# Top.net
KiCad netlist of a schematic drawn in Altium Designer
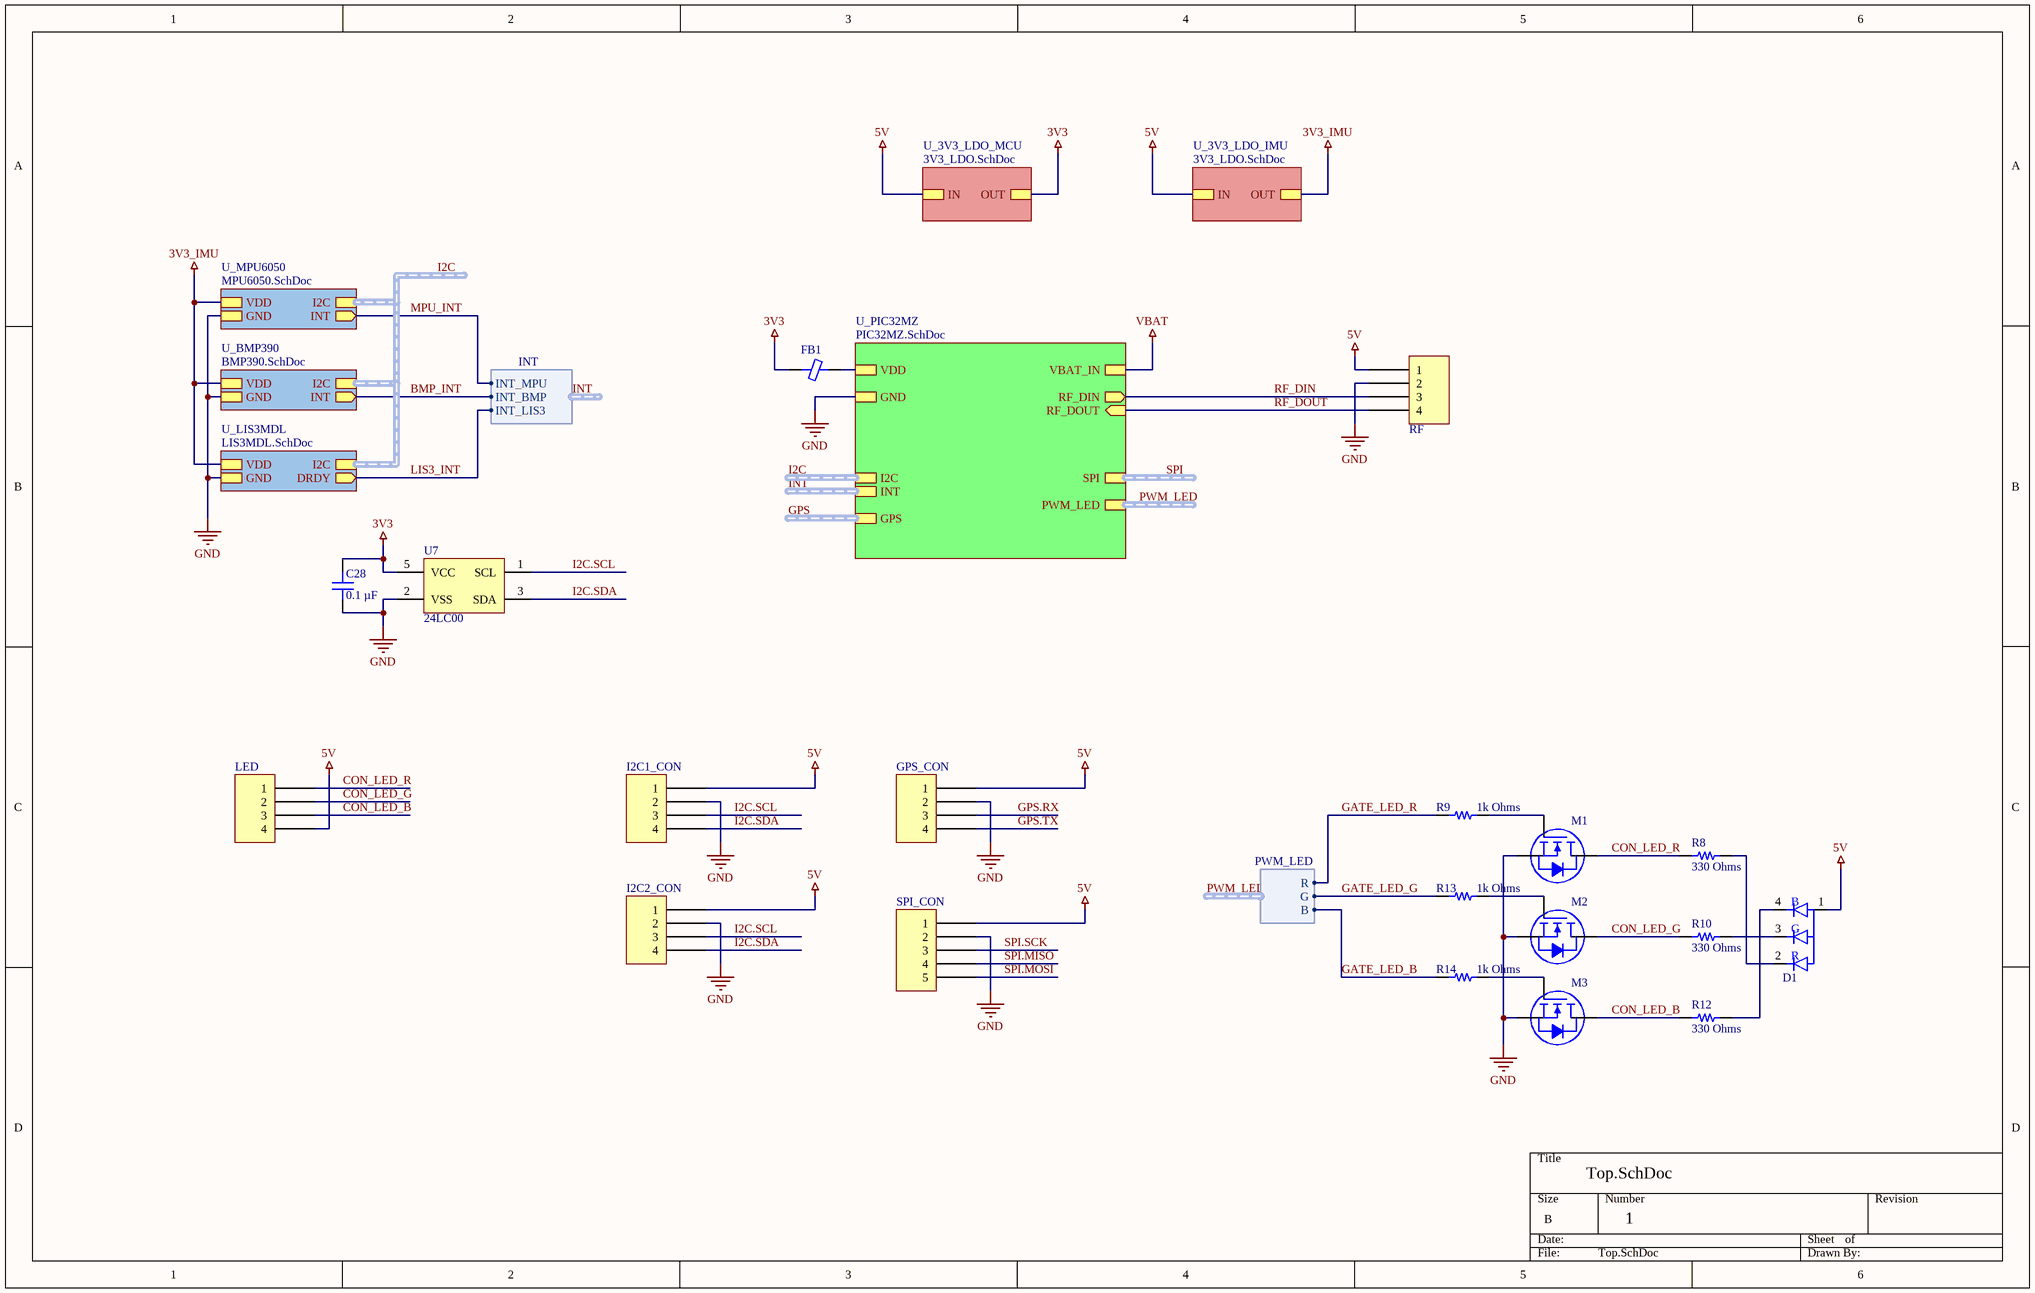
[diagram p0: Top.SchDoc]

(export (version "E")
  (design (tool "Eeschema 10.0.6"))
  (components
    (comp (ref "C28")
      (value "0.1 µF")
      (footprint "CAP 0402_1005")
      (description "CAP CER 0.1UF 16V X7R 0402")
      (fields (field (name "PART NUMBER") "C0402C104K4RACAUTO") (field (name "MANUFACTURER") "KEMET"))
      (libsource (lib "Celestial Altium Library - altium_library") (part "Capacitor"))
    )
    (comp (ref "D1")
      (value "RGB LED 3228")
      (footprint "CreeLED 3228")
      (description "DIODE LED RGB DIFFUSED 4LCC SMD CLV1L-FKB-CJ1N1E1BB7B3B3")
      (fields (field (name "MANUFACTURER") "Cree") (field (name "MOUSER PART NUMBER") "941-CLV1LFKBC7673673"))
      (libsource (lib "IC") (part "RGB LED 3228"))
    )
    (comp (ref "FB1")
      (value "~")
      (footprint "FER 0805_2012")
      (description "FERRITE BEAD 0805 1LN")
      (fields
        (field (name "PART NUMBER") "2508051017Y0")
        (field (name "MANUFACTURER") "Fair-Rite Products Corp.")
      )
      (libsource (lib "Celestial Altium Library - altium_library") (part "Ferrite Chip"))
    )
    (comp (ref "GPS_CON")
      (value "SM04B-SRSS-TB(LF)(SN)")
      (footprint "JST SM04B-SRSS-TB")
      (description "CONN HEADER SMD R/A 4POS 1MM")
      (fields (field (name "MANUFACTURER") "JST Sales America Inc."))
      (libsource (lib "Celestial Altium Library - altium_library") (part "4 Pin"))
    )
    (comp (ref "I2C1_CON")
      (value "SM04B-SRSS-TB(LF)(SN)")
      (footprint "JST SM04B-SRSS-TB")
      (description "CONN HEADER SMD R/A 4POS 1MM")
      (fields (field (name "MANUFACTURER") "JST Sales America Inc."))
      (libsource (lib "Celestial Altium Library - altium_library") (part "4 Pin"))
    )
    (comp (ref "I2C2_CON")
      (value "SM04B-SRSS-TB(LF)(SN)")
      (footprint "JST SM04B-SRSS-TB")
      (description "CONN HEADER SMD R/A 4POS 1MM")
      (fields (field (name "MANUFACTURER") "JST Sales America Inc."))
      (libsource (lib "Celestial Altium Library - altium_library") (part "4 Pin"))
    )
    (comp (ref "LED")
      (value "SM04B-SRSS-TB(LF)(SN)")
      (footprint "JST SM04B-SRSS-TB")
      (description "CONN HEADER SMD R/A 4POS 1MM")
      (fields (field (name "MANUFACTURER") "JST Sales America Inc."))
      (libsource (lib "Celestial Altium Library - altium_library") (part "4 Pin"))
    )
    (comp (ref "M1")
      (value "BSS123-7-F")
      (footprint "DIODES SOT-23-3")
      (description "MOSFET N-CH 100V 170MA SOT23-3")
      (fields (field (name "MANUFACTURER") "Diodes Incorporated"))
      (libsource (lib "Celestial Altium Library - altium_library") (part "DIODES INC MOSFET N-CH SOT-23-3"))
    )
    (comp (ref "M2")
      (value "BSS123-7-F")
      (footprint "DIODES SOT-23-3")
      (description "MOSFET N-CH 100V 170MA SOT23-3")
      (fields (field (name "MANUFACTURER") "Diodes Incorporated"))
      (libsource (lib "Celestial Altium Library - altium_library") (part "DIODES INC MOSFET N-CH SOT-23-3"))
    )
    (comp (ref "M3")
      (value "BSS123-7-F")
      (footprint "DIODES SOT-23-3")
      (description "MOSFET N-CH 100V 170MA SOT23-3")
      (fields (field (name "MANUFACTURER") "Diodes Incorporated"))
      (libsource (lib "Celestial Altium Library - altium_library") (part "DIODES INC MOSFET N-CH SOT-23-3"))
    )
    (comp (ref "R8")
      (value "330 Ohms")
      (footprint "RES 0603_1608")
      (description "RES 10K OHM 0.1% 1/16W 0603")
      (fields
        (field (name "PART NUMBER") "RNCS0603BKE10K0")
        (field (name "MANUFACTURER") "Stackpole Electronics Inc")
      )
      (libsource (lib "Celestial Altium Library - altium_library") (part "Resistor"))
    )
    (comp (ref "R9")
      (value "1k Ohms")
      (footprint "RES 0402_1005")
      (description "RES 330 OHM 5% 1/16W 0402")
      (fields (field (name "PART NUMBER") "CRCW0402330RJNEDC") (field (name "MANUFACTURER") "Vishay Dale"))
      (libsource (lib "Celestial Altium Library - altium_library") (part "Resistor"))
    )
    (comp (ref "R10")
      (value "330 Ohms")
      (footprint "RES 0603_1608")
      (description "RES 10K OHM 0.1% 1/16W 0603")
      (fields
        (field (name "PART NUMBER") "RNCS0603BKE10K0")
        (field (name "MANUFACTURER") "Stackpole Electronics Inc")
      )
      (libsource (lib "Celestial Altium Library - altium_library") (part "Resistor"))
    )
    (comp (ref "R12")
      (value "330 Ohms")
      (footprint "RES 0603_1608")
      (description "RES 10K OHM 0.1% 1/16W 0603")
      (fields
        (field (name "PART NUMBER") "RNCS0603BKE10K0")
        (field (name "MANUFACTURER") "Stackpole Electronics Inc")
      )
      (libsource (lib "Celestial Altium Library - altium_library") (part "Resistor"))
    )
    (comp (ref "R13")
      (value "1k Ohms")
      (footprint "RES 0402_1005")
      (description "RES 330 OHM 5% 1/16W 0402")
      (fields (field (name "PART NUMBER") "CRCW0402330RJNEDC") (field (name "MANUFACTURER") "Vishay Dale"))
      (libsource (lib "Celestial Altium Library - altium_library") (part "Resistor"))
    )
    (comp (ref "R14")
      (value "1k Ohms")
      (footprint "RES 0402_1005")
      (description "RES 330 OHM 5% 1/16W 0402")
      (fields (field (name "PART NUMBER") "CRCW0402330RJNEDC") (field (name "MANUFACTURER") "Vishay Dale"))
      (libsource (lib "Celestial Altium Library - altium_library") (part "Resistor"))
    )
    (comp (ref "RF")
      (value "SM04B-SRSS-TB(LF)(SN)")
      (footprint "JST SM04B-SRSS-TB")
      (description "CONN HEADER SMD R/A 4POS 1MM")
      (fields (field (name "MANUFACTURER") "JST Sales America Inc."))
      (libsource (lib "") (part "4 Pin_1"))
    )
    (comp (ref "SPI_CON")
      (value "SM05B-SRSS-TB(LF)(SN)")
      (footprint "JST SM05B-SRSS-TB")
      (description "CONN HEADER SMD R/A 5POS 1MM")
      (fields (field (name "MANUFACTURER") "JST Sales America Inc."))
      (libsource (lib "Celestial Altium Library - altium_library") (part "5 Pin"))
    )
    (comp (ref "U7")
      (value "24LC00")
      (footprint "SOT-23-5")
      (description "EEPROM")
      (libsource (lib "IC") (part "24LC00"))
    )
  )
  (nets
    (net (code "9") (name "/CON_LED_B") (class "Default")
      (node (ref "LED") (pin "3") (pinfunction "3_3") (pintype "passive"))
      (node (ref "M3") (pin "3") (pinfunction "D_3") (pintype "passive"))
      (node (ref "R12") (pin "1") (pinfunction "1_1") (pintype "passive"))
    )
    (net (code "10") (name "/CON_LED_G") (class "Default")
      (node (ref "LED") (pin "2") (pinfunction "2_2") (pintype "passive"))
      (node (ref "M2") (pin "3") (pinfunction "D_3") (pintype "passive"))
      (node (ref "R10") (pin "1") (pinfunction "1_1") (pintype "passive"))
    )
    (net (code "11") (name "/CON_LED_R") (class "Default")
      (node (ref "LED") (pin "1") (pinfunction "1_1") (pintype "passive"))
      (node (ref "M1") (pin "3") (pinfunction "D_3") (pintype "passive"))
      (node (ref "R8") (pin "1") (pinfunction "1_1") (pintype "passive"))
    )
    (net (code "12") (name "/GATE_LED_B") (class "Default")
      (node (ref "R14") (pin "2") (pinfunction "2_2") (pintype "passive"))
    )
    (net (code "13") (name "/GATE_LED_G") (class "Default")
      (node (ref "R13") (pin "2") (pinfunction "2_2") (pintype "passive"))
    )
    (net (code "14") (name "/GATE_LED_R") (class "Default")
      (node (ref "R9") (pin "2") (pinfunction "2_2") (pintype "passive"))
    )
    (net (code "15") (name "/GPS.RX") (class "Default")
      (node (ref "GPS_CON") (pin "3") (pinfunction "3_3") (pintype "passive"))
    )
    (net (code "16") (name "/GPS.TX") (class "Default")
      (node (ref "GPS_CON") (pin "4") (pinfunction "4_4") (pintype "passive"))
    )
    (net (code "17") (name "/I2C.SCL") (class "Default")
      (node (ref "I2C1_CON") (pin "3") (pinfunction "3_3") (pintype "passive"))
      (node (ref "I2C2_CON") (pin "3") (pinfunction "3_3") (pintype "passive"))
      (node (ref "U7") (pin "1") (pinfunction "SCL_1") (pintype "passive"))
    )
    (net (code "18") (name "/I2C.SDA") (class "Default")
      (node (ref "I2C1_CON") (pin "4") (pinfunction "4_4") (pintype "passive"))
      (node (ref "I2C2_CON") (pin "4") (pinfunction "4_4") (pintype "passive"))
      (node (ref "U7") (pin "3") (pinfunction "SDA_3") (pintype "passive"))
    )
    (net (code "23") (name "/RF_DIN") (class "Default")
      (node (ref "RF") (pin "3") (pinfunction "3_3") (pintype "passive"))
    )
    (net (code "24") (name "/RF_DOUT") (class "Default")
      (node (ref "RF") (pin "4") (pinfunction "4_4") (pintype "passive"))
    )
    (net (code "25") (name "/SPI.MISO") (class "Default")
      (node (ref "SPI_CON") (pin "4") (pinfunction "4_4") (pintype "passive"))
    )
    (net (code "26") (name "/SPI.MOSI") (class "Default")
      (node (ref "SPI_CON") (pin "5") (pinfunction "5_5") (pintype "passive"))
    )
    (net (code "27") (name "/SPI.SCK") (class "Default")
      (node (ref "SPI_CON") (pin "3") (pinfunction "3_3") (pintype "passive"))
    )
    (net (code "28") (name "/VDD") (class "Default")
      (node (ref "FB1") (pin "2") (pinfunction "2_2") (pintype "passive"))
    )
    (net (code "34") (name "3V3") (class "Default")
      (node (ref "C28") (pin "2") (pinfunction "2_2") (pintype "passive"))
      (node (ref "FB1") (pin "1") (pinfunction "1_1") (pintype "passive"))
      (node (ref "U7") (pin "5") (pinfunction "VCC_5") (pintype "passive"))
    )
    (net (code "36") (name "5V") (class "Default")
      (node (ref "D1") (pin "1") (pinfunction "A_1") (pintype "passive"))
      (node (ref "GPS_CON") (pin "1") (pinfunction "1_1") (pintype "passive"))
      (node (ref "I2C1_CON") (pin "1") (pinfunction "1_1") (pintype "passive"))
      (node (ref "I2C2_CON") (pin "1") (pinfunction "1_1") (pintype "passive"))
      (node (ref "LED") (pin "4") (pinfunction "4_4") (pintype "passive"))
      (node (ref "RF") (pin "1") (pinfunction "1_1") (pintype "passive"))
      (node (ref "SPI_CON") (pin "1") (pinfunction "1_1") (pintype "passive"))
    )
    (net (code "37") (name "GND") (class "Default")
      (node (ref "C28") (pin "1") (pinfunction "1_1") (pintype "passive"))
      (node (ref "GPS_CON") (pin "2") (pinfunction "2_2") (pintype "passive"))
      (node (ref "I2C1_CON") (pin "2") (pinfunction "2_2") (pintype "passive"))
      (node (ref "I2C2_CON") (pin "2") (pinfunction "2_2") (pintype "passive"))
      (node (ref "M1") (pin "2") (pinfunction "S_2") (pintype "passive"))
      (node (ref "M2") (pin "2") (pinfunction "S_2") (pintype "passive"))
      (node (ref "M3") (pin "2") (pinfunction "S_2") (pintype "passive"))
      (node (ref "RF") (pin "2") (pinfunction "2_2") (pintype "passive"))
      (node (ref "SPI_CON") (pin "2") (pinfunction "2_2") (pintype "passive"))
      (node (ref "U7") (pin "2") (pinfunction "VSS_2") (pintype "passive"))
    )
    (net (code "38") (name "Net-(D1-BLUE(C)-Pad2)") (class "Default")
      (node (ref "D1") (pin "2") (pinfunction "BLUE(C)_2") (pintype "passive"))
      (node (ref "R8") (pin "2") (pinfunction "2_2") (pintype "passive"))
    )
    (net (code "39") (name "Net-(D1-BLUE(C)-Pad3)") (class "Default")
      (node (ref "D1") (pin "3") (pinfunction "BLUE(C)_3") (pintype "passive"))
      (node (ref "R10") (pin "2") (pinfunction "2_2") (pintype "passive"))
    )
    (net (code "40") (name "Net-(D1-BLUE(C)-Pad4)") (class "Default")
      (node (ref "D1") (pin "4") (pinfunction "BLUE(C)_4") (pintype "passive"))
      (node (ref "R12") (pin "2") (pinfunction "2_2") (pintype "passive"))
    )
    (net (code "41") (name "Net-(M1-G)") (class "Default")
      (node (ref "M1") (pin "1") (pinfunction "G_1") (pintype "passive"))
      (node (ref "R9") (pin "1") (pinfunction "1_1") (pintype "passive"))
    )
    (net (code "42") (name "Net-(M2-G)") (class "Default")
      (node (ref "M2") (pin "1") (pinfunction "G_1") (pintype "passive"))
      (node (ref "R13") (pin "1") (pinfunction "1_1") (pintype "passive"))
    )
    (net (code "43") (name "Net-(M3-G)") (class "Default")
      (node (ref "M3") (pin "1") (pinfunction "G_1") (pintype "passive"))
      (node (ref "R14") (pin "1") (pinfunction "1_1") (pintype "passive"))
    )
  )
)
